# DriverSchematic.net
KiCad netlist of a schematic drawn in Altium Designer
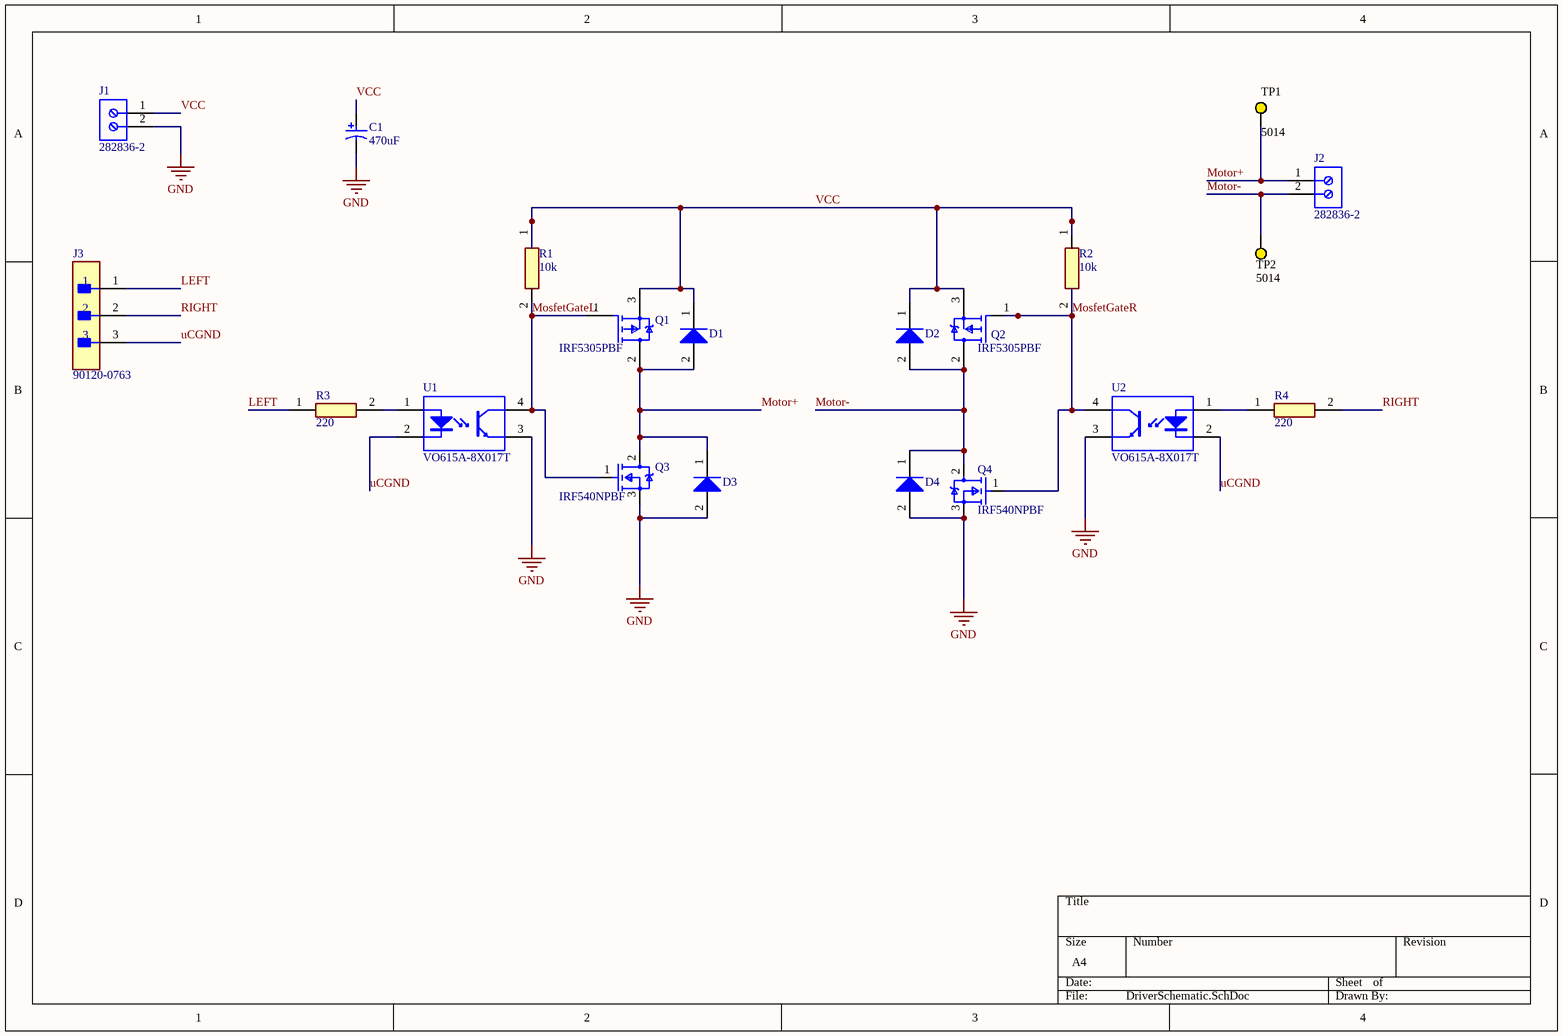
[diagram p0: DriverSchematic.SchDoc]

(export (version "E")
  (design (tool "Eeschema 10.0.6"))
  (components
    (comp (ref "C1")
      (value "470uF")
      (footprint "PNSC-CAP-10x20-P2")
      (description "Aluminum Electrolytic Capacitor, 470 uF, +/- 20%, 50 V, -55 to 105 degC, 2-Pin THD, RoHS, Bulk")
      (fields (field (name "MANUFACTURER") "Panasonic"))
      (libsource (lib "Altium Content Vault") (part "CAP-P-2"))
    )
    (comp (ref "D1")
      (value "MUR410RLG")
      (footprint "ONSC-AXIAL_LEAD-2-267-05_V")
      (description "SWITCHMODE(TM) Power Rectifier, 2-Pin Axial_Lead, Pb-Free, Tape and Reel")
      (fields (field (name "MANUFACTURER") "On Semiconductor"))
      (libsource (lib "Altium Content Vault") (part "ONSC-D-K1A2-2"))
    )
    (comp (ref "D2")
      (value "MUR410RLG")
      (footprint "ONSC-AXIAL_LEAD-2-267-05_V")
      (description "SWITCHMODE(TM) Power Rectifier, 2-Pin Axial_Lead, Pb-Free, Tape and Reel")
      (fields (field (name "MANUFACTURER") "On Semiconductor"))
      (libsource (lib "Altium Content Vault") (part "ONSC-D-K1A2-2"))
    )
    (comp (ref "D3")
      (value "MUR410RLG")
      (footprint "ONSC-AXIAL_LEAD-2-267-05_V")
      (description "SWITCHMODE(TM) Power Rectifier, 2-Pin Axial_Lead, Pb-Free, Tape and Reel")
      (fields (field (name "MANUFACTURER") "On Semiconductor"))
      (libsource (lib "Altium Content Vault") (part "ONSC-D-K1A2-2"))
    )
    (comp (ref "D4")
      (value "MUR410RLG")
      (footprint "ONSC-AXIAL_LEAD-2-267-05_V")
      (description "SWITCHMODE(TM) Power Rectifier, 2-Pin Axial_Lead, Pb-Free, Tape and Reel")
      (fields (field (name "MANUFACTURER") "On Semiconductor"))
      (libsource (lib "Altium Content Vault") (part "ONSC-D-K1A2-2"))
    )
    (comp (ref "J1")
      (value "282836-2")
      (footprint "TECO-282836-2_V")
      (description "Female Header, Pitch 5 mm, 1 x 2 Position, Height 10 mm, Tail Length 3.5 mm, Rohs, Bulk")
      (fields (field (name "VOLTAGE") "300V") (field (name "MANUFACTURER") "TE Connectivity"))
      (libsource (lib "Altium Content Vault") (part "CN-1P-F-TB2"))
    )
    (comp (ref "J2")
      (value "282836-2")
      (footprint "TECO-282836-2_V")
      (description "Female Header, Pitch 5 mm, 1 x 2 Position, Height 10 mm, Tail Length 3.5 mm, Rohs, Bulk")
      (fields (field (name "VOLTAGE") "300V") (field (name "MANUFACTURER") "TE Connectivity"))
      (libsource (lib "Altium Content Vault") (part "CN-1P-F-TB2"))
    )
    (comp (ref "J3")
      (value "90120-0763")
      (footprint "FP-90120-0763-MFG")
      (description "CONN HEADER VERT 3POS 2.54MM")
      (fields
        (field (name "MANUFACTURER") "Molex")
        (field (name "OCTOPART") "https://octopart.com/90120-0763-molex-655433")
      )
      (libsource (lib "Altium Content Vault") (part "0d3f023dd272f625e17a2be33dea85f"))
    )
    (comp (ref "Q1")
      (value "IRF5305PBF")
      (footprint "FP-PG-TO220-3-0")
      (description "MOSFET P-CH 55V 31A TO-220AB")
      (fields
        (field (name "OCTOPART") "https://octopart.com/irf5305pbf-infineon-65873396")
        (field (name "MANUFACTURER") "Infineon")
      )
      (libsource (lib "Altium Content Vault") (part "ef9d0aacdf366ab529cd174aea9d313"))
    )
    (comp (ref "Q2")
      (value "IRF5305PBF")
      (footprint "FP-PG-TO220-3-0")
      (description "MOSFET P-CH 55V 31A TO-220AB")
      (fields
        (field (name "OCTOPART") "https://octopart.com/irf5305pbf-infineon-65873396")
        (field (name "MANUFACTURER") "Infineon")
      )
      (libsource (lib "Altium Content Vault") (part "ef9d0aacdf366ab529cd174aea9d313"))
    )
    (comp (ref "Q3")
      (value "IRF540NPBF")
      (footprint "Infineon_IRF540NPBF_0")
      (description "TRANS MOSFET N-CH 100V 33A TO-220AB")
      (fields (field (name "MANUFACTURER") "Infineon") (field (name "MOUSER PART NUMBER") "942-IRF540NPBF"))
      (libsource (lib "Trans_Infineon_IRF540NPBF_eec") (part "Trans_Infineon_IRF540NPBF_eec"))
    )
    (comp (ref "Q4")
      (value "IRF540NPBF")
      (footprint "Infineon_IRF540NPBF_0")
      (description "TRANS MOSFET N-CH 100V 33A TO-220AB")
      (fields (field (name "MANUFACTURER") "Infineon") (field (name "MOUSER PART NUMBER") "942-IRF540NPBF"))
      (libsource (lib "Trans_Infineon_IRF540NPBF_eec") (part "Trans_Infineon_IRF540NPBF_eec"))
    )
    (comp (ref "R1")
      (value "10k")
      (footprint "SamacSys:RESAD3200W81L1200D500")
      (description "Resistor")
      (fields
        (field (name "MANUFACTURER_PART_NUMBER") "OM1035E-R58")
        (field (name "MOUSER PART NUMBER") "588-OM1035E-R58")
      )
      (libsource (lib "*") (part "OM1035E-R58"))
    )
    (comp (ref "R2")
      (value "10k")
      (footprint "SamacSys:RESAD3200W81L1200D500")
      (description "Resistor")
      (fields
        (field (name "MANUFACTURER_PART_NUMBER") "OM1035E-R58")
        (field (name "MOUSER PART NUMBER") "588-OM1035E-R58")
      )
      (libsource (lib "*") (part "OM1035E-R58"))
    )
    (comp (ref "R3")
      (value "220")
      (footprint "SamacSys:RESAD1650W60L650D250")
      (description "Resistor")
      (fields
        (field (name "MANUFACTURER_PART_NUMBER") "MRS25000C2200FCT00")
        (field (name "MOUSER PART NUMBER") "594-MRS25000C2200FCT")
      )
      (libsource (lib "*") (part "MRS25000C2200FCT00"))
    )
    (comp (ref "R4")
      (value "220")
      (footprint "SamacSys:RESAD1650W60L650D250")
      (description "Resistor")
      (fields
        (field (name "MANUFACTURER_PART_NUMBER") "MRS25000C2200FCT00")
        (field (name "MOUSER PART NUMBER") "594-MRS25000C2200FCT")
      )
      (libsource (lib "*") (part "MRS25000C2200FCT00"))
    )
    (comp (ref "TP1")
      (value "5014")
      (footprint "KSTN-5014_V")
      (description "Test Point, Yellow, Through Hole, RoHS, Bulk")
      (fields (field (name "MANUFACTURER") "Keystone"))
      (libsource (lib "Altium Content Vault") (part "TESTPOINT_YELLOW"))
    )
    (comp (ref "TP2")
      (value "5014")
      (footprint "KSTN-5014_V")
      (description "Test Point, Yellow, Through Hole, RoHS, Bulk")
      (fields (field (name "MANUFACTURER") "Keystone"))
      (libsource (lib "Altium Content Vault") (part "TESTPOINT_YELLOW"))
    )
    (comp (ref "U1")
      (value "VO615A-8X017T")
      (footprint "VISH-VO615A-XX017T_V")
      (fields (field (name "MANUFACTURER") "Vishay"))
      (libsource (lib "Altium Content Vault") (part "OPTO-AKEC-4"))
    )
    (comp (ref "U2")
      (value "VO615A-8X017T")
      (footprint "VISH-VO615A-XX017T_V")
      (fields (field (name "MANUFACTURER") "Vishay"))
      (libsource (lib "Altium Content Vault") (part "OPTO-AKEC-4"))
    )
  )
  (nets
    (net (code "1") (name "/LEFT") (class "Default")
      (node (ref "J3") (pin "1") (pinfunction "1_1") (pintype "passive"))
      (node (ref "R3") (pin "1") (pinfunction "1_1") (pintype "passive"))
    )
    (net (code "2") (name "/MosfetGateL") (class "Default")
      (node (ref "Q1") (pin "1") (pinfunction "G_1") (pintype "passive"))
      (node (ref "Q3") (pin "1") (pinfunction "GATE_1") (pintype "passive"))
      (node (ref "R1") (pin "2") (pinfunction "2_2") (pintype "passive"))
      (node (ref "U1") (pin "4") (pinfunction "COLLECTOR_4") (pintype "passive"))
    )
    (net (code "3") (name "/MosfetGateR") (class "Default")
      (node (ref "Q2") (pin "1") (pinfunction "G_1") (pintype "passive"))
      (node (ref "Q4") (pin "1") (pinfunction "GATE_1") (pintype "passive"))
      (node (ref "R2") (pin "2") (pinfunction "2_2") (pintype "passive"))
      (node (ref "U2") (pin "4") (pinfunction "COLLECTOR_4") (pintype "passive"))
    )
    (net (code "4") (name "/Motor+") (class "Default")
      (node (ref "D1") (pin "2") (pinfunction "A_2") (pintype "passive"))
      (node (ref "D3") (pin "1") (pinfunction "K_1") (pintype "passive"))
      (node (ref "J2") (pin "1") (pinfunction "1_1") (pintype "passive"))
      (node (ref "Q1") (pin "2") (pinfunction "D_2") (pintype "passive"))
      (node (ref "Q3") (pin "2") (pinfunction "DRAIN_2") (pintype "passive"))
      (node (ref "TP1") (pin "1") (pinfunction "1_1") (pintype "passive"))
    )
    (net (code "5") (name "/Motor-") (class "Default")
      (node (ref "D2") (pin "2") (pinfunction "A_2") (pintype "passive"))
      (node (ref "D4") (pin "1") (pinfunction "K_1") (pintype "passive"))
      (node (ref "J2") (pin "2") (pinfunction "2_2") (pintype "passive"))
      (node (ref "Q2") (pin "2") (pinfunction "D_2") (pintype "passive"))
      (node (ref "Q4") (pin "2") (pinfunction "DRAIN_2") (pintype "passive"))
      (node (ref "TP2") (pin "1") (pinfunction "1_1") (pintype "passive"))
    )
    (net (code "6") (name "/RIGHT") (class "Default")
      (node (ref "J3") (pin "2") (pinfunction "2_2") (pintype "passive"))
      (node (ref "R4") (pin "2") (pinfunction "2_2") (pintype "passive"))
    )
    (net (code "7") (name "/VCC") (class "Default")
      (node (ref "C1") (pin "1") (pinfunction "1_1") (pintype "passive"))
      (node (ref "D1") (pin "1") (pinfunction "K_1") (pintype "passive"))
      (node (ref "D2") (pin "1") (pinfunction "K_1") (pintype "passive"))
      (node (ref "J1") (pin "1") (pinfunction "1_1") (pintype "passive"))
      (node (ref "Q1") (pin "3") (pinfunction "S_3") (pintype "passive"))
      (node (ref "Q2") (pin "3") (pinfunction "S_3") (pintype "passive"))
      (node (ref "R1") (pin "1") (pinfunction "1_1") (pintype "passive"))
      (node (ref "R2") (pin "1") (pinfunction "1_1") (pintype "passive"))
    )
    (net (code "8") (name "/uCGND") (class "Default")
      (node (ref "J3") (pin "3") (pinfunction "3_3") (pintype "passive"))
      (node (ref "U1") (pin "2") (pinfunction "CATHODE_2") (pintype "passive"))
      (node (ref "U2") (pin "2") (pinfunction "CATHODE_2") (pintype "passive"))
    )
    (net (code "9") (name "GND") (class "Default")
      (node (ref "C1") (pin "2") (pinfunction "2_2") (pintype "passive"))
      (node (ref "D3") (pin "2") (pinfunction "A_2") (pintype "passive"))
      (node (ref "D4") (pin "2") (pinfunction "A_2") (pintype "passive"))
      (node (ref "J1") (pin "2") (pinfunction "2_2") (pintype "passive"))
      (node (ref "Q3") (pin "3") (pinfunction "SOURCE_3") (pintype "passive"))
      (node (ref "Q4") (pin "3") (pinfunction "SOURCE_3") (pintype "passive"))
      (node (ref "U1") (pin "3") (pinfunction "EMITTER_3") (pintype "passive"))
      (node (ref "U2") (pin "3") (pinfunction "EMITTER_3") (pintype "passive"))
    )
    (net (code "10") (name "Net-(U1-ANODE)") (class "Default")
      (node (ref "R3") (pin "2") (pinfunction "2_2") (pintype "passive"))
      (node (ref "U1") (pin "1") (pinfunction "ANODE_1") (pintype "passive"))
    )
    (net (code "11") (name "Net-(U2-ANODE)") (class "Default")
      (node (ref "R4") (pin "1") (pinfunction "1_1") (pintype "passive"))
      (node (ref "U2") (pin "1") (pinfunction "ANODE_1") (pintype "passive"))
    )
  )
)
